# CH32V467VET-USB.net
KiCad netlist of a schematic drawn in Altium Designer
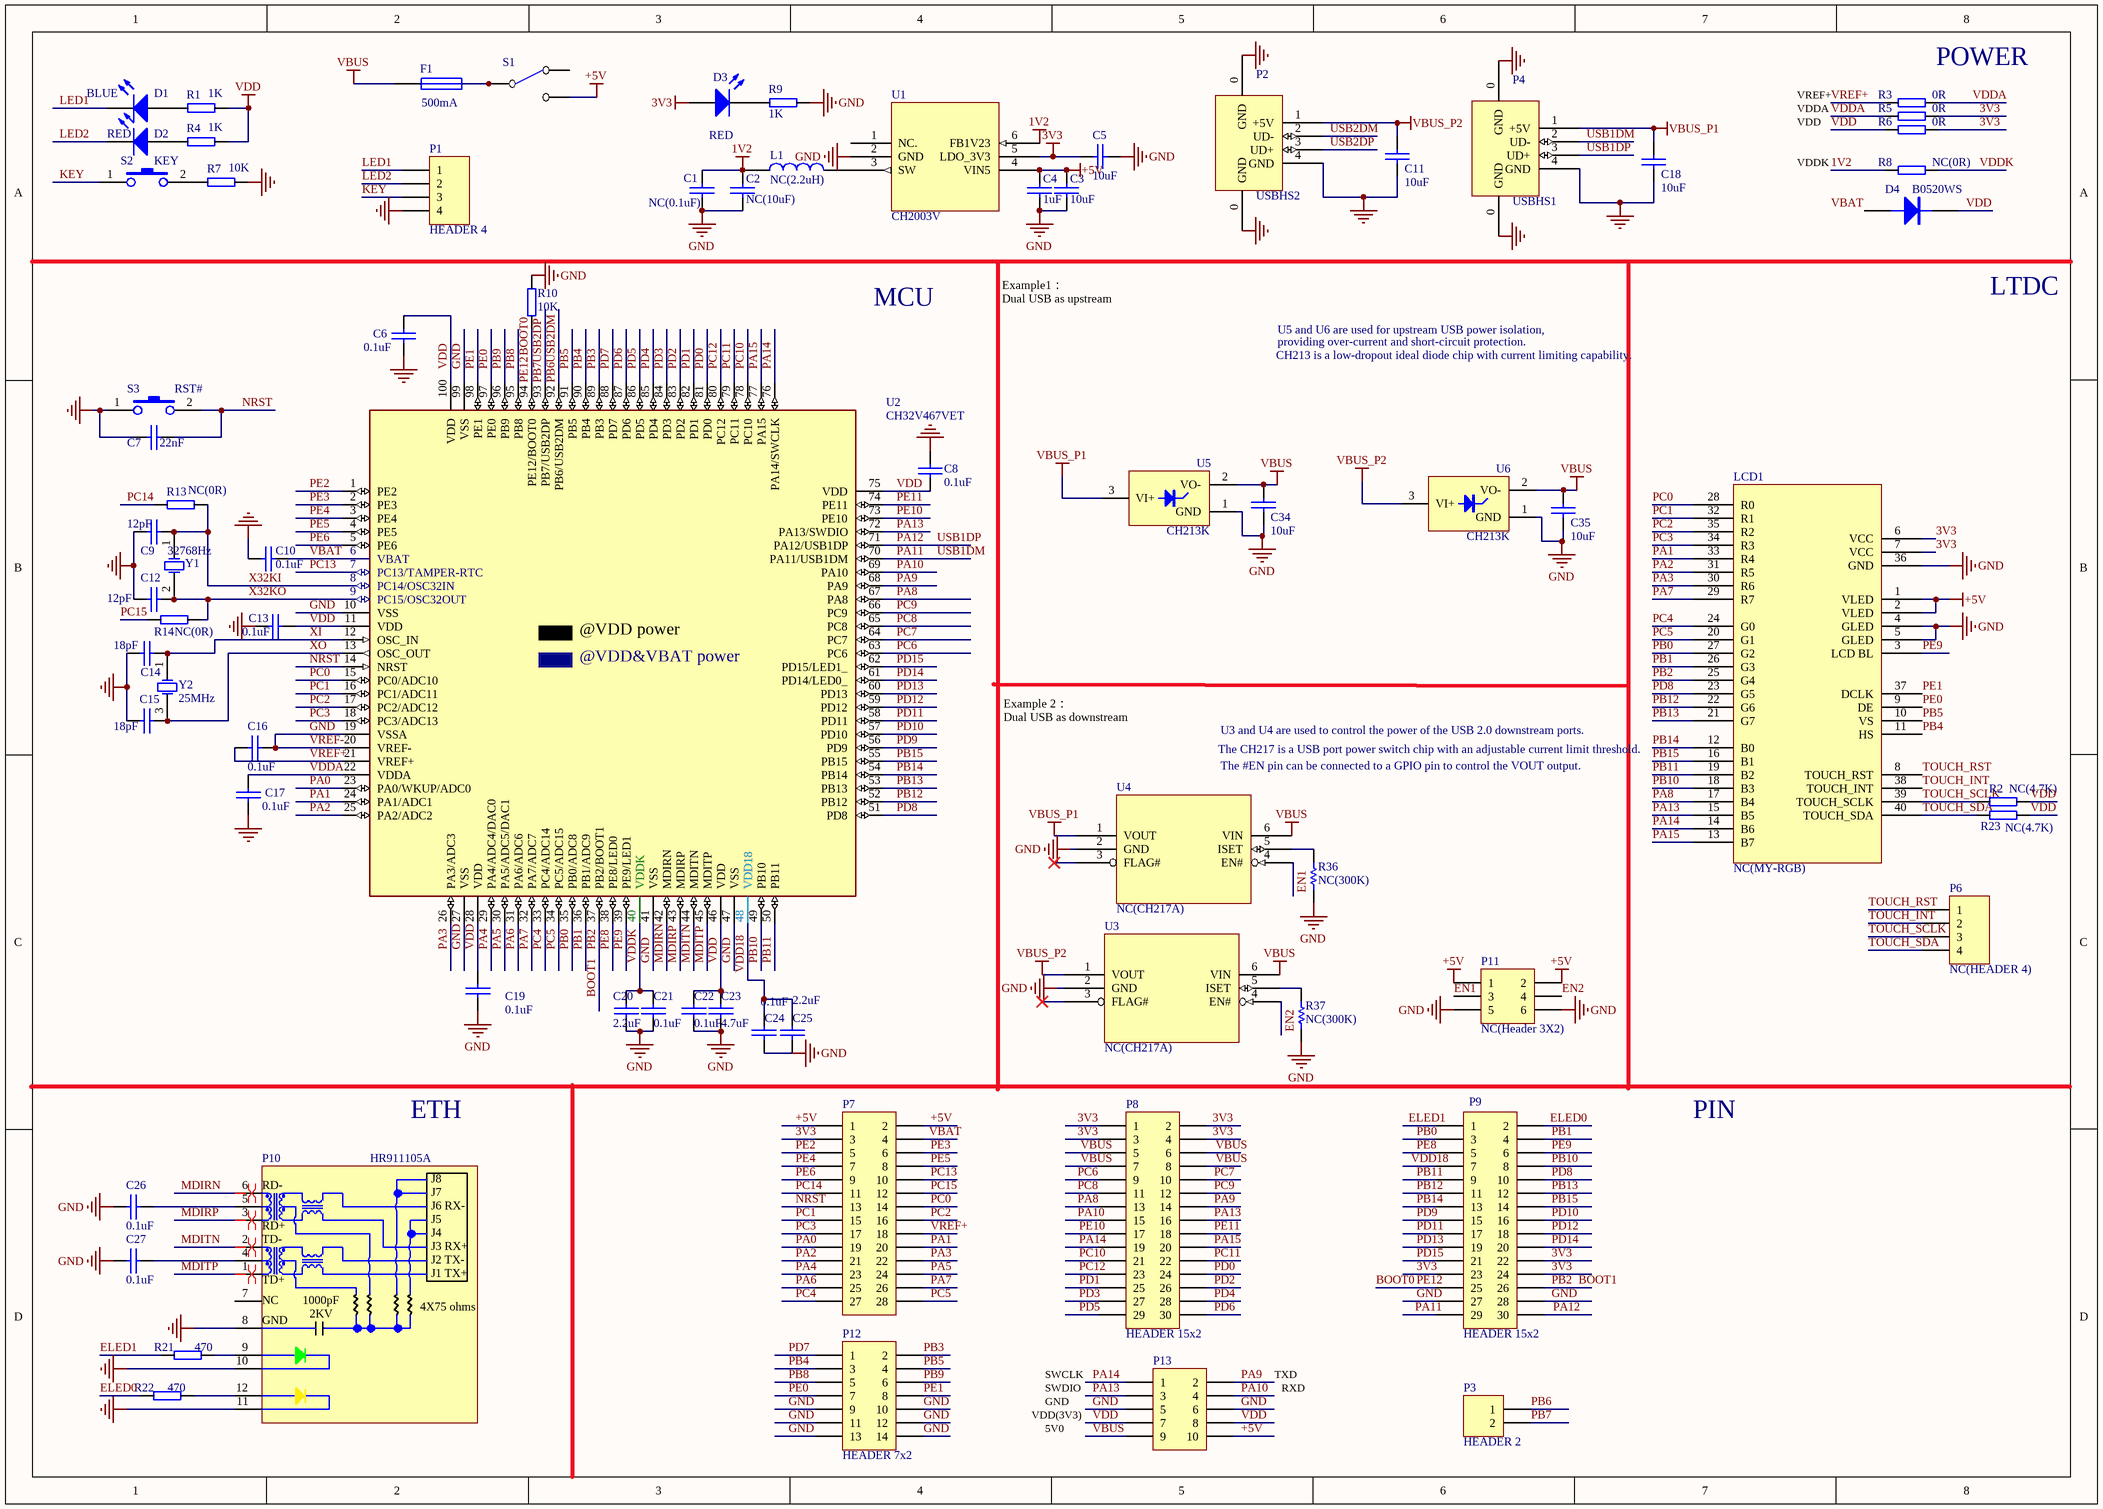
[diagram p0: CH32V467VET-USB.SchDoc]

(export (version "E")
  (design (tool "Eeschema 10.0.6"))
  (components
    (comp (ref "C1")
      (value "NC(0.1uF)")
      (footprint "0402_C")
      (description "Capacitor")
      (libsource (lib "") (part "CAP_2"))
    )
    (comp (ref "C2")
      (value "NC(10uF)")
      (footprint "0603_C")
      (description "Capacitor")
      (libsource (lib "*") (part "CAP"))
    )
    (comp (ref "C3")
      (value "10uF")
      (footprint "0603_C")
      (description "Capacitor")
      (libsource (lib "*") (part "CAP"))
    )
    (comp (ref "C4")
      (value "1uF")
      (footprint "0402_C")
      (description "Capacitor")
      (libsource (lib "") (part "CAP_2"))
    )
    (comp (ref "C5")
      (value "10uF")
      (footprint "0603_C")
      (description "Capacitor")
      (libsource (lib "*") (part "CAP"))
    )
    (comp (ref "C6")
      (value "0.1uF")
      (footprint "0402_C")
      (description "Capacitor")
      (libsource (lib "*") (part "CAP"))
    )
    (comp (ref "C7")
      (value "22nF")
      (footprint "0402_C")
      (description "Capacitor")
      (libsource (lib "") (part "CAP_1"))
    )
    (comp (ref "C8")
      (value "0.1uF")
      (footprint "0402_C")
      (description "Capacitor")
      (libsource (lib "*") (part "CAP"))
    )
    (comp (ref "C9")
      (value "12pF")
      (footprint "0402_C")
      (description "Capacitor")
      (libsource (lib "*") (part "CAP"))
    )
    (comp (ref "C10")
      (value "0.1uF")
      (footprint "0402_C")
      (description "Capacitor")
      (libsource (lib "*") (part "CAP"))
    )
    (comp (ref "C11")
      (value "10uF")
      (footprint "0603_C")
      (description "Capacitor")
      (libsource (lib "") (part "CAP_1"))
    )
    (comp (ref "C12")
      (value "12pF")
      (footprint "0402_C")
      (description "Capacitor")
      (libsource (lib "*") (part "CAP"))
    )
    (comp (ref "C13")
      (value "0.1uF")
      (footprint "0402_C")
      (description "Capacitor")
      (libsource (lib "*") (part "CAP"))
    )
    (comp (ref "C14")
      (value "18pF")
      (footprint "0402_C")
      (description "Capacitor")
      (libsource (lib "*") (part "CAP"))
    )
    (comp (ref "C15")
      (value "18pF")
      (footprint "0402_C")
      (description "Capacitor")
      (libsource (lib "*") (part "CAP"))
    )
    (comp (ref "C16")
      (value "0.1uF")
      (footprint "0402_C")
      (description "Capacitor")
      (libsource (lib "*") (part "CAP"))
    )
    (comp (ref "C17")
      (value "0.1uF")
      (footprint "0402_C")
      (description "Capacitor")
      (libsource (lib "*") (part "CAP"))
    )
    (comp (ref "C18")
      (value "10uF")
      (footprint "0603_C")
      (description "Capacitor")
      (libsource (lib "") (part "CAP_1"))
    )
    (comp (ref "C19")
      (value "0.1uF")
      (footprint "0402_C")
      (description "Capacitor")
      (libsource (lib "*") (part "CAP"))
    )
    (comp (ref "C20")
      (value "2.2uF")
      (footprint "0402_C")
      (description "Capacitor")
      (libsource (lib "*") (part "CAP"))
    )
    (comp (ref "C21")
      (value "0.1uF")
      (footprint "0402_C")
      (description "Capacitor")
      (libsource (lib "*") (part "CAP"))
    )
    (comp (ref "C22")
      (value "0.1uF")
      (footprint "0402_C")
      (description "Capacitor")
      (libsource (lib "*") (part "CAP"))
    )
    (comp (ref "C23")
      (value "4.7uF")
      (footprint "0402_C")
      (description "Capacitor")
      (libsource (lib "*") (part "CAP"))
    )
    (comp (ref "C24")
      (value "0.1uF")
      (footprint "0402_C")
      (description "Capacitor")
      (libsource (lib "*") (part "CAP"))
    )
    (comp (ref "C25")
      (value "2.2uF")
      (footprint "0402_C")
      (description "Capacitor")
      (libsource (lib "*") (part "CAP"))
    )
    (comp (ref "C26")
      (value "0.1uF")
      (footprint "0402_C")
      (description "Capacitor")
      (libsource (lib "wch_sch_others") (part "CAP"))
    )
    (comp (ref "C27")
      (value "0.1uF")
      (footprint "0402_C")
      (description "Capacitor")
      (libsource (lib "wch_sch_others") (part "CAP"))
    )
    (comp (ref "C34")
      (value "10uF")
      (footprint "0603_C")
      (description "Capacitor")
      (libsource (lib "") (part "CAP_1"))
    )
    (comp (ref "C35")
      (value "10uF")
      (footprint "0603_C")
      (description "Capacitor")
      (libsource (lib "") (part "CAP_1"))
    )
    (comp (ref "D1")
      (value "BLUE")
      (footprint "0603+")
      (description "Typical INFRARED GaAs LED")
      (fields (field (name "PUBLISHER") "Altium Limited"))
      (libsource (lib "*") (part "LED0"))
    )
    (comp (ref "D2")
      (value "RED")
      (footprint "0603+")
      (description "Typical INFRARED GaAs LED")
      (fields (field (name "PUBLISHER") "Altium Limited"))
      (libsource (lib "*") (part "LED0"))
    )
    (comp (ref "D3")
      (value "RED")
      (footprint "0603+")
      (description "Typical INFRARED GaAs LED")
      (fields (field (name "PUBLISHER") "Altium Limited"))
      (libsource (lib "*") (part "LED0"))
    )
    (comp (ref "D4")
      (value "B0520WS")
      (footprint "SOD-323")
      (description "Diode")
      (libsource (lib "*") (part "DIODE"))
    )
    (comp (ref "F1")
      (value "500mA")
      (footprint "0603")
      (description "Fuse")
      (libsource (lib "wch_sch_others") (part "FUSE1"))
    )
    (comp (ref "L1") (value "NC(2.2uH)") (footprint "CD32") (libsource (lib "*") (part "INDUCTOR")))
    (comp (ref "LCD1")
      (value "NC(MY-RGB)")
      (footprint "FPC40P-0.5-FK750M3")
      (libsource (lib "MY-显示") (part "MY-RGB"))
    )
    (comp (ref "P1")
      (value "HEADER 4")
      (footprint "SIP4-2.54mm")
      (description "Header, 4-Pin")
      (libsource (lib "wch_sch_others") (part "HEADER 4"))
    )
    (comp (ref "P2")
      (value "USBHS2")
      (footprint "USBAF")
      (description "USB Port")
      (libsource (lib "*") (part "USB"))
    )
    (comp (ref "P3")
      (value "HEADER 2")
      (footprint "MYPCB:SIP2-2.54mm")
      (description "Header, 2-Pin")
      (libsource (lib "wch_sch_others") (part "HEADER 2"))
    )
    (comp (ref "P4")
      (value "USBHS1")
      (footprint "USBAF")
      (description "USB Port")
      (libsource (lib "*") (part "USB"))
    )
    (comp (ref "P6")
      (value "NC(HEADER 4)")
      (footprint "SIP4-2.54mm")
      (description "Header, 4-Pin")
      (libsource (lib "wch_sch_others") (part "HEADER 4"))
    )
    (comp (ref "P7")
      (value "HEADER 14x2")
      (footprint "MYPCB:IDC28-2.54MM")
      (description "Header, 14-Pin, Dual row")
      (libsource (lib "wch_sch_others") (part "HEADER 14x2"))
    )
    (comp (ref "P8")
      (value "HEADER 15x2")
      (footprint "MYPCB:IDC30-2.54MM")
      (description "Header, 15-Pin, Dual row")
      (libsource (lib "wch_sch_others") (part "HEADER 15x2"))
    )
    (comp (ref "P9")
      (value "HEADER 15x2")
      (footprint "MYPCB:IDC30-2.54MM")
      (description "Header, 15-Pin, Dual row")
      (libsource (lib "wch_sch_others") (part "HEADER 15x2"))
    )
    (comp (ref "P10") (value "HR911105A") (footprint "HR911105A") (libsource (lib "*") (part "HR911105A")))
    (comp (ref "P11")
      (value "NC(Header 3X2)")
      (footprint "HDR2X3")
      (description "Header, 3-Pin, Dual row")
      (fields (field (name "PUBLISHER") "Altium Limited"))
      (libsource (lib "Miscellaneous Connectors") (part "Header 3X2"))
    )
    (comp (ref "P12")
      (value "HEADER 7x2")
      (footprint "MYPCB:IDC14-2.54mm")
      (description "Header, 7-Pin, Dual row")
      (libsource (lib "wch_sch_others") (part "HEADER 7x2"))
    )
    (comp (ref "P13")
      (value "LINK")
      (footprint "IDC10-2.54mm")
      (description "Header, 5-Pin, Dual row, Right Angle")
      (fields (field (name "PUBLISHER") "Altium Limited"))
      (libsource (lib "Miscellaneous Connectors") (part "Header 5X2H"))
    )
    (comp (ref "R1") (value "1K") (footprint "0402") (libsource (lib "wch_sch_others") (part "RES")))
    (comp (ref "R2") (value "NC(4.7K)") (footprint "0402") (libsource (lib "wch_sch_others") (part "RES")))
    (comp (ref "R3") (value "0R") (footprint "0402") (libsource (lib "*") (part "R")))
    (comp (ref "R4") (value "1K") (footprint "0402") (libsource (lib "wch_sch_others") (part "RES")))
    (comp (ref "R5") (value "0R") (footprint "0402") (libsource (lib "*") (part "R")))
    (comp (ref "R6") (value "0R") (footprint "0402") (libsource (lib "*") (part "R")))
    (comp (ref "R7") (value "10K") (footprint "0402") (libsource (lib "wch_sch_others") (part "RES")))
    (comp (ref "R8") (value "NC(0R)") (footprint "0402") (libsource (lib "*") (part "R")))
    (comp (ref "R9") (value "1K") (footprint "0402") (libsource (lib "wch_sch_others") (part "RES")))
    (comp (ref "R10") (value "10K") (footprint "0402") (libsource (lib "wch_sch_others") (part "RES")))
    (comp (ref "R13") (value "NC(0R)") (footprint "0402") (libsource (lib "wch_sch_others") (part "RES")))
    (comp (ref "R14") (value "NC(0R)") (footprint "0402") (libsource (lib "wch_sch_others") (part "RES")))
    (comp (ref "R21") (value "470") (footprint "0402") (libsource (lib "wch_sch_others") (part "RES")))
    (comp (ref "R22") (value "470") (footprint "0402") (libsource (lib "wch_sch_others") (part "RES")))
    (comp (ref "R23") (value "NC(4.7K)") (footprint "0402") (libsource (lib "wch_sch_others") (part "RES")))
    (comp (ref "R36")
      (value "NC(300K)")
      (footprint "0603")
      (description "Resistor")
      (fields (field (name "PUBLISHER") "Altium Limited"))
      (libsource (lib "MYLIB") (part "0603-1"))
    )
    (comp (ref "R37")
      (value "NC(300K)")
      (footprint "0603")
      (description "Resistor")
      (fields (field (name "PUBLISHER") "Altium Limited"))
      (libsource (lib "MYLIB") (part "0603-1"))
    )
    (comp (ref "S1") (value "SW SPDT") (footprint "SW1") (libsource (lib "*") (part "SW SPDT")))
    (comp (ref "S2")
      (value "KEY")
      (footprint "SMD_6.1x3.65x2.5mm-KEY")
      (libsource (lib "wch_sch_others") (part "KEY1"))
    )
    (comp (ref "S3")
      (value "RST#")
      (footprint "SMD_6.1x3.65x2.5mm-KEY")
      (libsource (lib "wch_sch_others") (part "KEY1"))
    )
    (comp (ref "U1")
      (value "CH2003V")
      (footprint "SOT-23-6")
      (description "Step-Down DC-DC Converter, 5V input, 1.23V * 800mA output, with LDO 3.3V * 200mA")
      (libsource (lib "CHXXX") (part "CH2003V"))
    )
    (comp (ref "U2")
      (value "CH32V467VET")
      (footprint "LQFP100")
      (description "RISC-V FPU HD-MCU, 175MHz, USB_480M, 100M Ethernet & Phy, CAN, DVP, ADC, DAC, SRAM")
      (libsource (lib "CHXXX") (part "CH32V467VET"))
    )
    (comp (ref "U3")
      (value "NC(CH217A)")
      (footprint "SOT-23-6")
      (description "Current-Limited USB Power Distribution Switch")
      (libsource (lib "CHXXX") (part "CH217K"))
    )
    (comp (ref "U4")
      (value "NC(CH217A)")
      (footprint "SOT-23-6")
      (description "Current-Limited USB Power Distribution Switch")
      (libsource (lib "CHXXX") (part "CH217K"))
    )
    (comp (ref "U5")
      (value "CH213K")
      (footprint "SOT-23-3")
      (description "Ideal Diode 5V*1A")
      (libsource (lib "*") (part "CH213K"))
    )
    (comp (ref "U6")
      (value "CH213K")
      (footprint "SOT-23-3")
      (description "Ideal Diode 5V*1A")
      (libsource (lib "*") (part "CH213K"))
    )
    (comp (ref "Y1")
      (value "32768Hz")
      (footprint "FC-135")
      (description "Crystal Oscillator")
      (fields (field (name "PUBLISHER") "Altium Limited"))
      (libsource (lib "*") (part "XTAL"))
    )
    (comp (ref "Y2")
      (value "25MHz")
      (footprint "XT3225")
      (description "Crystal Oscillator")
      (fields (field (name "PUBLISHER") "Altium Limited"))
      (libsource (lib "") (part "XTAL_1"))
    )
  )
  (nets
    (net (code "1") (name "+5V") (class "Default")
      (node (ref "C3") (pin "2") (pinfunction "2_2") (pintype "passive"))
      (node (ref "C4") (pin "2") (pinfunction "2_2") (pintype "passive"))
      (node (ref "LCD1") (pin "1") (pinfunction "VLED_1") (pintype "passive"))
      (node (ref "LCD1") (pin "2") (pinfunction "VLED_2") (pintype "passive"))
      (node (ref "P11") (pin "1") (pinfunction "1_1") (pintype "passive"))
      (node (ref "P11") (pin "2") (pinfunction "2_2") (pintype "passive"))
      (node (ref "P13") (pin "10") (pinfunction "10_10") (pintype "passive"))
      (node (ref "P7") (pin "1") (pinfunction "1_1") (pintype "passive"))
      (node (ref "P7") (pin "2") (pinfunction "2_2") (pintype "passive"))
      (node (ref "S1") (pin "2") (pinfunction "NC_2") (pintype "passive"))
      (node (ref "U1") (pin "4") (pinfunction "VIN5_4") (pintype "power_in"))
    )
    (net (code "3") (name "/BOOT0") (class "Default")
      (node (ref "P9") (pin "25") (pinfunction "25_25") (pintype "passive"))
      (node (ref "R10") (pin "2") (pintype "passive"))
      (node (ref "U2") (pin "94") (pinfunction "PE12/BOOT0_94") (pintype "bidirectional"))
    )
    (net (code "4") (name "/BOOT1") (class "Default")
      (node (ref "LCD1") (pin "25") (pinfunction "G4_25") (pintype "passive"))
      (node (ref "P9") (pin "26") (pinfunction "26_26") (pintype "passive"))
      (node (ref "U2") (pin "37") (pinfunction "PB2/BOOT1_37") (pintype "bidirectional"))
    )
    (net (code "5") (name "/ELED0") (class "Default")
      (node (ref "P9") (pin "2") (pinfunction "2_2") (pintype "passive"))
      (node (ref "R22") (pin "1") (pintype "passive"))
    )
    (net (code "6") (name "/ELED1") (class "Default")
      (node (ref "P9") (pin "1") (pinfunction "1_1") (pintype "passive"))
      (node (ref "R21") (pin "1") (pintype "passive"))
    )
    (net (code "7") (name "/EN1") (class "Default")
      (node (ref "P11") (pin "3") (pinfunction "3_3") (pintype "passive"))
      (node (ref "U4") (pin "4") (pinfunction "EN#_4") (pintype "input"))
    )
    (net (code "8") (name "/EN2") (class "Default")
      (node (ref "P11") (pin "4") (pinfunction "4_4") (pintype "passive"))
      (node (ref "U3") (pin "4") (pinfunction "EN#_4") (pintype "input"))
    )
    (net (code "9") (name "/KEY") (class "Default")
      (node (ref "P1") (pin "3") (pinfunction "3_3") (pintype "passive"))
      (node (ref "S2") (pin "1") (pinfunction "1_1") (pintype "passive"))
    )
    (net (code "10") (name "/LED1") (class "Default")
      (node (ref "D1") (pin "2") (pinfunction "K_2") (pintype "passive"))
      (node (ref "P1") (pin "1") (pinfunction "1_1") (pintype "passive"))
    )
    (net (code "11") (name "/LED2") (class "Default")
      (node (ref "D2") (pin "2") (pinfunction "K_2") (pintype "passive"))
      (node (ref "P1") (pin "2") (pinfunction "2_2") (pintype "passive"))
    )
    (net (code "12") (name "/MDIRN") (class "Default")
      (node (ref "P10") (pin "6") (pintype "passive"))
      (node (ref "U2") (pin "42") (pinfunction "MDIRN_42") (pintype "bidirectional"))
    )
    (net (code "13") (name "/MDIRP") (class "Default")
      (node (ref "P10") (pin "3") (pintype "passive"))
      (node (ref "U2") (pin "43") (pinfunction "MDIRP_43") (pintype "bidirectional"))
    )
    (net (code "14") (name "/MDITN") (class "Default")
      (node (ref "P10") (pin "2") (pintype "passive"))
      (node (ref "U2") (pin "44") (pinfunction "MDITN_44") (pintype "bidirectional"))
    )
    (net (code "15") (name "/MDITP") (class "Default")
      (node (ref "P10") (pin "1") (pintype "passive"))
      (node (ref "U2") (pin "45") (pinfunction "MDITP_45") (pintype "bidirectional"))
    )
    (net (code "16") (name "/NRST") (class "Default")
      (node (ref "C7") (pin "2") (pinfunction "2_2") (pintype "passive"))
      (node (ref "P7") (pin "13") (pinfunction "13_13") (pintype "passive"))
      (node (ref "S3") (pin "2") (pinfunction "2_2") (pintype "passive"))
      (node (ref "U2") (pin "14") (pinfunction "NRST_14") (pintype "input"))
    )
    (net (code "17") (name "/PA0") (class "Default")
      (node (ref "P7") (pin "19") (pinfunction "19_19") (pintype "passive"))
      (node (ref "U2") (pin "23") (pinfunction "PA0/WKUP/ADC0_23") (pintype "bidirectional"))
    )
    (net (code "18") (name "/PA1") (class "Default")
      (node (ref "LCD1") (pin "33") (pinfunction "R4_33") (pintype "passive"))
      (node (ref "P7") (pin "20") (pinfunction "20_20") (pintype "passive"))
      (node (ref "U2") (pin "24") (pinfunction "PA1/ADC1_24") (pintype "bidirectional"))
    )
    (net (code "19") (name "/PA2") (class "Default")
      (node (ref "LCD1") (pin "31") (pinfunction "R5_31") (pintype "passive"))
      (node (ref "P7") (pin "21") (pinfunction "21_21") (pintype "passive"))
      (node (ref "U2") (pin "25") (pinfunction "PA2/ADC2_25") (pintype "bidirectional"))
    )
    (net (code "20") (name "/PA3") (class "Default")
      (node (ref "LCD1") (pin "30") (pinfunction "R6_30") (pintype "passive"))
      (node (ref "P7") (pin "22") (pinfunction "22_22") (pintype "passive"))
      (node (ref "U2") (pin "26") (pinfunction "PA3/ADC3_26") (pintype "bidirectional"))
    )
    (net (code "21") (name "/PA4") (class "Default")
      (node (ref "P7") (pin "23") (pinfunction "23_23") (pintype "passive"))
      (node (ref "U2") (pin "29") (pinfunction "PA4/ADC4/DAC0_29") (pintype "bidirectional"))
    )
    (net (code "22") (name "/PA5") (class "Default")
      (node (ref "P7") (pin "24") (pinfunction "24_24") (pintype "passive"))
      (node (ref "U2") (pin "30") (pinfunction "PA5/ADC5/DAC1_30") (pintype "bidirectional"))
    )
    (net (code "23") (name "/PA6") (class "Default")
      (node (ref "P7") (pin "25") (pinfunction "25_25") (pintype "passive"))
      (node (ref "U2") (pin "31") (pinfunction "PA6/ADC6_31") (pintype "bidirectional"))
    )
    (net (code "24") (name "/PA7") (class "Default")
      (node (ref "LCD1") (pin "29") (pinfunction "R7_29") (pintype "passive"))
      (node (ref "P7") (pin "26") (pinfunction "26_26") (pintype "passive"))
      (node (ref "U2") (pin "32") (pinfunction "PA7/ADC7_32") (pintype "bidirectional"))
    )
    (net (code "25") (name "/PA8") (class "Default")
      (node (ref "LCD1") (pin "17") (pinfunction "B4_17") (pintype "passive"))
      (node (ref "P8") (pin "13") (pinfunction "13_13") (pintype "passive"))
      (node (ref "U2") (pin "67") (pinfunction "PA8_67") (pintype "bidirectional"))
    )
    (net (code "26") (name "/PA9") (class "Default")
      (node (ref "P13") (pin "2") (pinfunction "2_2") (pintype "passive"))
      (node (ref "P8") (pin "14") (pinfunction "14_14") (pintype "passive"))
      (node (ref "U2") (pin "68") (pinfunction "PA9_68") (pintype "bidirectional"))
    )
    (net (code "27") (name "/PA10") (class "Default")
      (node (ref "P13") (pin "4") (pinfunction "4_4") (pintype "passive"))
      (node (ref "P8") (pin "15") (pinfunction "15_15") (pintype "passive"))
      (node (ref "U2") (pin "69") (pinfunction "PA10_69") (pintype "bidirectional"))
    )
    (net (code "28") (name "/PA11") (class "Default")
      (node (ref "P4") (pin "2") (pinfunction "UD-_2") (pintype "bidirectional"))
      (node (ref "P9") (pin "29") (pinfunction "29_29") (pintype "passive"))
      (node (ref "U2") (pin "70") (pinfunction "PA11/USB1DM_70") (pintype "bidirectional"))
    )
    (net (code "29") (name "/PA12") (class "Default")
      (node (ref "P4") (pin "3") (pinfunction "UD+_3") (pintype "bidirectional"))
      (node (ref "P9") (pin "30") (pinfunction "30_30") (pintype "passive"))
      (node (ref "U2") (pin "71") (pinfunction "PA12/USB1DP_71") (pintype "bidirectional"))
    )
    (net (code "30") (name "/PA13") (class "Default")
      (node (ref "LCD1") (pin "15") (pinfunction "B5_15") (pintype "passive"))
      (node (ref "P13") (pin "3") (pinfunction "3_3") (pintype "passive"))
      (node (ref "P8") (pin "16") (pinfunction "16_16") (pintype "passive"))
      (node (ref "U2") (pin "72") (pinfunction "PA13/SWDIO_72") (pintype "bidirectional"))
    )
    (net (code "31") (name "/PA14") (class "Default")
      (node (ref "LCD1") (pin "14") (pinfunction "B6_14") (pintype "passive"))
      (node (ref "P13") (pin "1") (pinfunction "1_1") (pintype "passive"))
      (node (ref "P8") (pin "19") (pinfunction "19_19") (pintype "passive"))
      (node (ref "U2") (pin "76") (pinfunction "PA14/SWCLK_76") (pintype "bidirectional"))
    )
    (net (code "32") (name "/PA15") (class "Default")
      (node (ref "LCD1") (pin "13") (pinfunction "B7_13") (pintype "passive"))
      (node (ref "P8") (pin "20") (pinfunction "20_20") (pintype "passive"))
      (node (ref "U2") (pin "77") (pinfunction "PA15_77") (pintype "bidirectional"))
    )
    (net (code "33") (name "/PB0") (class "Default")
      (node (ref "LCD1") (pin "27") (pinfunction "G2_27") (pintype "passive"))
      (node (ref "P9") (pin "3") (pinfunction "3_3") (pintype "passive"))
      (node (ref "U2") (pin "35") (pinfunction "PB0/ADC8_35") (pintype "bidirectional"))
    )
    (net (code "34") (name "/PB1") (class "Default")
      (node (ref "LCD1") (pin "26") (pinfunction "G3_26") (pintype "passive"))
      (node (ref "P9") (pin "4") (pinfunction "4_4") (pintype "passive"))
      (node (ref "U2") (pin "36") (pinfunction "PB1/ADC9_36") (pintype "bidirectional"))
    )
    (net (code "35") (name "/PB3") (class "Default")
      (node (ref "P12") (pin "2") (pinfunction "2_2") (pintype "passive"))
      (node (ref "U2") (pin "89") (pinfunction "PB3_89") (pintype "bidirectional"))
    )
    (net (code "36") (name "/PB4") (class "Default")
      (node (ref "LCD1") (pin "11") (pinfunction "HS_11") (pintype "passive"))
      (node (ref "P12") (pin "3") (pinfunction "3_3") (pintype "passive"))
      (node (ref "U2") (pin "90") (pinfunction "PB4_90") (pintype "bidirectional"))
    )
    (net (code "37") (name "/PB5") (class "Default")
      (node (ref "LCD1") (pin "10") (pinfunction "VS_10") (pintype "passive"))
      (node (ref "P12") (pin "4") (pinfunction "4_4") (pintype "passive"))
      (node (ref "U2") (pin "91") (pinfunction "PB5_91") (pintype "bidirectional"))
    )
    (net (code "38") (name "/PB6") (class "Default")
      (node (ref "P2") (pin "2") (pinfunction "UD-_2") (pintype "bidirectional"))
      (node (ref "P3") (pin "1") (pinfunction "1_1") (pintype "passive"))
      (node (ref "U2") (pin "92") (pinfunction "PB6/USB2DM_92") (pintype "bidirectional"))
    )
    (net (code "39") (name "/PB7") (class "Default")
      (node (ref "P2") (pin "3") (pinfunction "UD+_3") (pintype "bidirectional"))
      (node (ref "P3") (pin "2") (pinfunction "2_2") (pintype "passive"))
      (node (ref "U2") (pin "93") (pinfunction "PB7/USB2DP_93") (pintype "bidirectional"))
    )
    (net (code "40") (name "/PB8") (class "Default")
      (node (ref "P12") (pin "5") (pinfunction "5_5") (pintype "passive"))
      (node (ref "U2") (pin "95") (pinfunction "PB8_95") (pintype "bidirectional"))
    )
    (net (code "41") (name "/PB9") (class "Default")
      (node (ref "P12") (pin "6") (pinfunction "6_6") (pintype "passive"))
      (node (ref "U2") (pin "96") (pinfunction "PB9_96") (pintype "bidirectional"))
    )
    (net (code "42") (name "/PB10") (class "Default")
      (node (ref "LCD1") (pin "18") (pinfunction "B3_18") (pintype "passive"))
      (node (ref "P9") (pin "8") (pinfunction "8_8") (pintype "passive"))
      (node (ref "U2") (pin "49") (pinfunction "PB10_49") (pintype "bidirectional"))
    )
    (net (code "43") (name "/PB11") (class "Default")
      (node (ref "LCD1") (pin "19") (pinfunction "B2_19") (pintype "passive"))
      (node (ref "P9") (pin "9") (pinfunction "9_9") (pintype "passive"))
      (node (ref "U2") (pin "50") (pinfunction "PB11_50") (pintype "bidirectional"))
    )
    (net (code "44") (name "/PB12") (class "Default")
      (node (ref "LCD1") (pin "22") (pinfunction "G6_22") (pintype "passive"))
      (node (ref "P9") (pin "11") (pinfunction "11_11") (pintype "passive"))
      (node (ref "U2") (pin "52") (pinfunction "PB12_52") (pintype "bidirectional"))
    )
    (net (code "45") (name "/PB13") (class "Default")
      (node (ref "LCD1") (pin "21") (pinfunction "G7_21") (pintype "passive"))
      (node (ref "P9") (pin "12") (pinfunction "12_12") (pintype "passive"))
      (node (ref "U2") (pin "53") (pinfunction "PB13_53") (pintype "bidirectional"))
    )
    (net (code "46") (name "/PB14") (class "Default")
      (node (ref "LCD1") (pin "12") (pinfunction "B0_12") (pintype "passive"))
      (node (ref "P9") (pin "13") (pinfunction "13_13") (pintype "passive"))
      (node (ref "U2") (pin "54") (pinfunction "PB14_54") (pintype "bidirectional"))
    )
    (net (code "47") (name "/PB15") (class "Default")
      (node (ref "LCD1") (pin "16") (pinfunction "B1_16") (pintype "passive"))
      (node (ref "P9") (pin "14") (pinfunction "14_14") (pintype "passive"))
      (node (ref "U2") (pin "55") (pinfunction "PB15_55") (pintype "bidirectional"))
    )
    (net (code "48") (name "/PC0") (class "Default")
      (node (ref "LCD1") (pin "28") (pinfunction "R0_28") (pintype "passive"))
      (node (ref "P7") (pin "14") (pinfunction "14_14") (pintype "passive"))
      (node (ref "U2") (pin "15") (pinfunction "PC0/ADC10_15") (pintype "bidirectional"))
    )
    (net (code "49") (name "/PC1") (class "Default")
      (node (ref "LCD1") (pin "32") (pinfunction "R1_32") (pintype "passive"))
      (node (ref "P7") (pin "15") (pinfunction "15_15") (pintype "passive"))
      (node (ref "U2") (pin "16") (pinfunction "PC1/ADC11_16") (pintype "bidirectional"))
    )
    (net (code "50") (name "/PC2") (class "Default")
      (node (ref "LCD1") (pin "35") (pinfunction "R2_35") (pintype "passive"))
      (node (ref "P7") (pin "16") (pinfunction "16_16") (pintype "passive"))
      (node (ref "U2") (pin "17") (pinfunction "PC2/ADC12_17") (pintype "bidirectional"))
    )
    (net (code "51") (name "/PC3") (class "Default")
      (node (ref "LCD1") (pin "34") (pinfunction "R3_34") (pintype "passive"))
      (node (ref "P7") (pin "17") (pinfunction "17_17") (pintype "passive"))
      (node (ref "U2") (pin "18") (pinfunction "PC3/ADC13_18") (pintype "bidirectional"))
    )
    (net (code "52") (name "/PC4") (class "Default")
      (node (ref "LCD1") (pin "24") (pinfunction "G0_24") (pintype "passive"))
      (node (ref "P7") (pin "27") (pinfunction "27_27") (pintype "passive"))
      (node (ref "U2") (pin "33") (pinfunction "PC4/ADC14_33") (pintype "bidirectional"))
    )
    (net (code "53") (name "/PC5") (class "Default")
      (node (ref "LCD1") (pin "20") (pinfunction "G1_20") (pintype "passive"))
      (node (ref "P7") (pin "28") (pinfunction "28_28") (pintype "passive"))
      (node (ref "U2") (pin "34") (pinfunction "PC5/ADC15_34") (pintype "bidirectional"))
    )
    (net (code "54") (name "/PC6") (class "Default")
      (node (ref "P8") (pin "9") (pinfunction "9_9") (pintype "passive"))
      (node (ref "U2") (pin "63") (pinfunction "PC6_63") (pintype "bidirectional"))
    )
    (net (code "55") (name "/PC7") (class "Default")
      (node (ref "P8") (pin "10") (pinfunction "10_10") (pintype "passive"))
      (node (ref "U2") (pin "64") (pinfunction "PC7_64") (pintype "bidirectional"))
    )
    (net (code "56") (name "/PC8") (class "Default")
      (node (ref "P8") (pin "11") (pinfunction "11_11") (pintype "passive"))
      (node (ref "U2") (pin "65") (pinfunction "PC8_65") (pintype "bidirectional"))
    )
    (net (code "57") (name "/PC9") (class "Default")
      (node (ref "P8") (pin "12") (pinfunction "12_12") (pintype "passive"))
      (node (ref "U2") (pin "66") (pinfunction "PC9_66") (pintype "bidirectional"))
    )
    (net (code "58") (name "/PC10") (class "Default")
      (node (ref "P8") (pin "21") (pinfunction "21_21") (pintype "passive"))
      (node (ref "U2") (pin "78") (pinfunction "PC10_78") (pintype "bidirectional"))
    )
    (net (code "59") (name "/PC11") (class "Default")
      (node (ref "P8") (pin "22") (pinfunction "22_22") (pintype "passive"))
      (node (ref "U2") (pin "79") (pinfunction "PC11_79") (pintype "bidirectional"))
    )
    (net (code "60") (name "/PC12") (class "Default")
      (node (ref "P8") (pin "23") (pinfunction "23_23") (pintype "passive"))
      (node (ref "U2") (pin "80") (pinfunction "PC12_80") (pintype "bidirectional"))
    )
    (net (code "61") (name "/PC13") (class "Default")
      (node (ref "P7") (pin "10") (pinfunction "10_10") (pintype "passive"))
      (node (ref "U2") (pin "7") (pinfunction "PC13/TAMPER-RTC_7") (pintype "bidirectional"))
    )
    (net (code "62") (name "/PC14") (class "Default")
      (node (ref "P7") (pin "11") (pinfunction "11_11") (pintype "passive"))
      (node (ref "R13") (pin "1") (pintype "passive"))
    )
    (net (code "63") (name "/PC15") (class "Default")
      (node (ref "P7") (pin "12") (pinfunction "12_12") (pintype "passive"))
      (node (ref "R14") (pin "1") (pintype "passive"))
    )
    (net (code "64") (name "/PD0") (class "Default")
      (node (ref "P8") (pin "24") (pinfunction "24_24") (pintype "passive"))
      (node (ref "U2") (pin "81") (pinfunction "PD0_81") (pintype "bidirectional"))
    )
    (net (code "65") (name "/PD1") (class "Default")
      (node (ref "P8") (pin "25") (pinfunction "25_25") (pintype "passive"))
      (node (ref "U2") (pin "82") (pinfunction "PD1_82") (pintype "bidirectional"))
    )
    (net (code "66") (name "/PD2") (class "Default")
      (node (ref "P8") (pin "26") (pinfunction "26_26") (pintype "passive"))
      (node (ref "U2") (pin "83") (pinfunction "PD2_83") (pintype "bidirectional"))
    )
    (net (code "67") (name "/PD3") (class "Default")
      (node (ref "P8") (pin "27") (pinfunction "27_27") (pintype "passive"))
      (node (ref "U2") (pin "84") (pinfunction "PD3_84") (pintype "bidirectional"))
    )
    (net (code "68") (name "/PD4") (class "Default")
      (node (ref "P8") (pin "28") (pinfunction "28_28") (pintype "passive"))
      (node (ref "U2") (pin "85") (pinfunction "PD4_85") (pintype "bidirectional"))
    )
    (net (code "69") (name "/PD5") (class "Default")
      (node (ref "P8") (pin "29") (pinfunction "29_29") (pintype "passive"))
      (node (ref "U2") (pin "86") (pinfunction "PD5_86") (pintype "bidirectional"))
    )
    (net (code "70") (name "/PD6") (class "Default")
      (node (ref "P8") (pin "30") (pinfunction "30_30") (pintype "passive"))
      (node (ref "U2") (pin "87") (pinfunction "PD6_87") (pintype "bidirectional"))
    )
    (net (code "71") (name "/PD7") (class "Default")
      (node (ref "P12") (pin "1") (pinfunction "1_1") (pintype "passive"))
      (node (ref "U2") (pin "88") (pinfunction "PD7_88") (pintype "bidirectional"))
    )
    (net (code "72") (name "/PD8") (class "Default")
      (node (ref "LCD1") (pin "23") (pinfunction "G5_23") (pintype "passive"))
      (node (ref "P9") (pin "10") (pinfunction "10_10") (pintype "passive"))
      (node (ref "U2") (pin "51") (pinfunction "PD8_51") (pintype "bidirectional"))
    )
    (net (code "73") (name "/PD9") (class "Default")
      (node (ref "P9") (pin "15") (pinfunction "15_15") (pintype "passive"))
      (node (ref "U2") (pin "56") (pinfunction "PD9_56") (pintype "bidirectional"))
    )
    (net (code "74") (name "/PD10") (class "Default")
      (node (ref "P9") (pin "16") (pinfunction "16_16") (pintype "passive"))
      (node (ref "U2") (pin "57") (pinfunction "PD10_57") (pintype "bidirectional"))
    )
    (net (code "75") (name "/PD11") (class "Default")
      (node (ref "P9") (pin "17") (pinfunction "17_17") (pintype "passive"))
      (node (ref "U2") (pin "58") (pinfunction "PD11_58") (pintype "bidirectional"))
    )
    (net (code "76") (name "/PD12") (class "Default")
      (node (ref "P9") (pin "18") (pinfunction "18_18") (pintype "passive"))
      (node (ref "U2") (pin "59") (pinfunction "PD12_59") (pintype "bidirectional"))
    )
    (net (code "77") (name "/PD13") (class "Default")
      (node (ref "P9") (pin "19") (pinfunction "19_19") (pintype "passive"))
      (node (ref "U2") (pin "60") (pinfunction "PD13_60") (pintype "bidirectional"))
    )
    (net (code "78") (name "/PD14") (class "Default")
      (node (ref "P9") (pin "20") (pinfunction "20_20") (pintype "passive"))
      (node (ref "U2") (pin "61") (pinfunction "PD14/LED0__61") (pintype "bidirectional"))
    )
    (net (code "79") (name "/PD15") (class "Default")
      (node (ref "P9") (pin "21") (pinfunction "21_21") (pintype "passive"))
      (node (ref "U2") (pin "62") (pinfunction "PD15/LED1__62") (pintype "bidirectional"))
    )
    (net (code "80") (name "/PE0") (class "Default")
      (node (ref "LCD1") (pin "9") (pinfunction "DE_9") (pintype "passive"))
      (node (ref "P12") (pin "7") (pinfunction "7_7") (pintype "passive"))
      (node (ref "U2") (pin "97") (pinfunction "PE0_97") (pintype "bidirectional"))
    )
    (net (code "81") (name "/PE1") (class "Default")
      (node (ref "LCD1") (pin "37") (pinfunction "DCLK_37") (pintype "passive"))
      (node (ref "P12") (pin "8") (pinfunction "8_8") (pintype "passive"))
      (node (ref "U2") (pin "98") (pinfunction "PE1_98") (pintype "bidirectional"))
    )
    (net (code "82") (name "/PE2") (class "Default")
      (node (ref "P7") (pin "5") (pinfunction "5_5") (pintype "passive"))
      (node (ref "U2") (pin "1") (pinfunction "PE2_1") (pintype "bidirectional"))
    )
    (net (code "83") (name "/PE3") (class "Default")
      (node (ref "P7") (pin "6") (pinfunction "6_6") (pintype "passive"))
      (node (ref "U2") (pin "2") (pinfunction "PE3_2") (pintype "bidirectional"))
    )
    (net (code "84") (name "/PE4") (class "Default")
      (node (ref "P7") (pin "7") (pinfunction "7_7") (pintype "passive"))
      (node (ref "U2") (pin "3") (pinfunction "PE4_3") (pintype "bidirectional"))
    )
    (net (code "85") (name "/PE5") (class "Default")
      (node (ref "P7") (pin "8") (pinfunction "8_8") (pintype "passive"))
      (node (ref "U2") (pin "4") (pinfunction "PE5_4") (pintype "bidirectional"))
    )
    (net (code "86") (name "/PE6") (class "Default")
      (node (ref "P7") (pin "9") (pinfunction "9_9") (pintype "passive"))
      (node (ref "U2") (pin "5") (pinfunction "PE6_5") (pintype "bidirectional"))
    )
    (net (code "87") (name "/PE8") (class "Default")
      (node (ref "P9") (pin "5") (pinfunction "5_5") (pintype "passive"))
      (node (ref "U2") (pin "38") (pinfunction "PE8/LED0_38") (pintype "bidirectional"))
    )
    (net (code "88") (name "/PE9") (class "Default")
      (node (ref "LCD1") (pin "3") (pinfunction "LCD_BL_3") (pintype "passive"))
      (node (ref "P9") (pin "6") (pinfunction "6_6") (pintype "passive"))
      (node (ref "U2") (pin "39") (pinfunction "PE9/LED1_39") (pintype "bidirectional"))
    )
    (net (code "89") (name "/PE10") (class "Default")
      (node (ref "P8") (pin "17") (pinfunction "17_17") (pintype "passive"))
      (node (ref "U2") (pin "73") (pinfunction "PE10_73") (pintype "bidirectional"))
    )
    (net (code "90") (name "/PE11") (class "Default")
      (node (ref "P8") (pin "18") (pinfunction "18_18") (pintype "passive"))
      (node (ref "U2") (pin "74") (pinfunction "PE11_74") (pintype "bidirectional"))
    )
    (net (code "91") (name "/TOUCH_INT") (class "Default")
      (node (ref "LCD1") (pin "38") (pinfunction "TOUCH_INT_38") (pintype "passive"))
      (node (ref "P6") (pin "2") (pinfunction "2_2") (pintype "passive"))
    )
    (net (code "92") (name "/TOUCH_RST") (class "Default")
      (node (ref "LCD1") (pin "8") (pinfunction "TOUCH_RST_8") (pintype "passive"))
      (node (ref "P6") (pin "1") (pinfunction "1_1") (pintype "passive"))
    )
    (net (code "93") (name "/TOUCH_SCLK") (class "Default")
      (node (ref "LCD1") (pin "39") (pinfunction "TOUCH_SCLK_39") (pintype "passive"))
      (node (ref "P6") (pin "3") (pinfunction "3_3") (pintype "passive"))
      (node (ref "R2") (pin "2") (pintype "passive"))
    )
    (net (code "94") (name "/TOUCH_SDA") (class "Default")
      (node (ref "LCD1") (pin "40") (pinfunction "TOUCH_SDA_40") (pintype "passive"))
      (node (ref "P6") (pin "4") (pinfunction "4_4") (pintype "passive"))
      (node (ref "R23") (pin "2") (pintype "passive"))
    )
    (net (code "95") (name "/VBAT") (class "Default")
      (node (ref "C10") (pin "2") (pinfunction "2_2") (pintype "passive"))
      (node (ref "P7") (pin "4") (pinfunction "4_4") (pintype "passive"))
      (node (ref "U2") (pin "6") (pinfunction "VBAT_6") (pintype "power_in"))
    )
    (net (code "96") (name "/VDD18") (class "Default")
      (node (ref "C24") (pin "2") (pinfunction "2_2") (pintype "passive"))
      (node (ref "C25") (pin "2") (pinfunction "2_2") (pintype "passive"))
      (node (ref "P9") (pin "7") (pinfunction "7_7") (pintype "passive"))
      (node (ref "U2") (pin "48") (pinfunction "VDD18_48") (pintype "power_in"))
    )
    (net (code "97") (name "/VDDA") (class "Default")
      (node (ref "C17") (pin "1") (pinfunction "1_1") (pintype "passive"))
      (node (ref "R3") (pin "1") (pinfunction "1_1") (pintype "passive"))
      (node (ref "R5") (pin "2") (pinfunction "2_2") (pintype "passive"))
      (node (ref "U2") (pin "22") (pinfunction "VDDA_22") (pintype "power_in"))
    )
    (net (code "98") (name "/VDDK") (class "Default")
      (node (ref "C20") (pin "2") (pinfunction "2_2") (pintype "passive"))
      (node (ref "C21") (pin "2") (pinfunction "2_2") (pintype "passive"))
      (node (ref "R8") (pin "1") (pinfunction "1_1") (pintype "passive"))
      (node (ref "U2") (pin "40") (pinfunction "VDDK_40") (pintype "power_in"))
    )
    (net (code "99") (name "/VREF+") (class "Default")
      (node (ref "C16") (pin "1") (pinfunction "1_1") (pintype "passive"))
      (node (ref "P7") (pin "18") (pinfunction "18_18") (pintype "passive"))
      (node (ref "R3") (pin "2") (pinfunction "2_2") (pintype "passive"))
      (node (ref "U2") (pin "21") (pinfunction "VREF+_21") (pintype "power_in"))
    )
    (net (code "100") (name "/X32KI") (class "Default")
      (node (ref "C9") (pin "2") (pinfunction "2_2") (pintype "passive"))
      (node (ref "R13") (pin "2") (pintype "passive"))
      (node (ref "U2") (pin "8") (pinfunction "PC14/OSC32IN_8") (pintype "bidirectional"))
      (node (ref "Y1") (pin "1") (pinfunction "OSC1_1") (pintype "passive"))
    )
    (net (code "101") (name "/X32KO") (class "Default")
      (node (ref "C12") (pin "2") (pinfunction "2_2") (pintype "passive"))
      (node (ref "R14") (pin "2") (pintype "passive"))
      (node (ref "U2") (pin "9") (pinfunction "PC15/OSC32OUT_9") (pintype "bidirectional"))
      (node (ref "Y1") (pin "2") (pinfunction "OSC2_2") (pintype "passive"))
    )
    (net (code "102") (name "/XI") (class "Default")
      (node (ref "C14") (pin "2") (pinfunction "2_2") (pintype "passive"))
      (node (ref "U2") (pin "12") (pinfunction "OSC_IN_12") (pintype "input"))
      (node (ref "Y2") (pin "1") (pinfunction "OSC1_1") (pintype "passive"))
    )
    (net (code "103") (name "/XO") (class "Default")
      (node (ref "C15") (pin "2") (pinfunction "2_2") (pintype "passive"))
      (node (ref "U2") (pin "13") (pinfunction "OSC_OUT_13") (pintype "output"))
      (node (ref "Y2") (pin "3") (pinfunction "OSC2_3") (pintype "passive"))
    )
    (net (code "104") (name "1V2") (class "Default")
      (node (ref "C1") (pin "2") (pinfunction "2_2") (pintype "passive"))
      (node (ref "C2") (pin "2") (pinfunction "2_2") (pintype "passive"))
      (node (ref "L1") (pin "2") (pinfunction "2_2") (pintype "passive"))
      (node (ref "R8") (pin "2") (pinfunction "2_2") (pintype "passive"))
      (node (ref "U1") (pin "6") (pinfunction "FB1V23_6") (pintype "input"))
    )
    (net (code "105") (name "3V3") (class "Default")
      (node (ref "C5") (pin "2") (pinfunction "2_2") (pintype "passive"))
      (node (ref "D3") (pin "1") (pinfunction "A_1") (pintype "passive"))
      (node (ref "LCD1") (pin "6") (pinfunction "VCC_6") (pintype "passive"))
      (node (ref "LCD1") (pin "7") (pinfunction "VCC_7") (pintype "passive"))
      (node (ref "P7") (pin "3") (pinfunction "3_3") (pintype "passive"))
      (node (ref "P8") (pin "1") (pinfunction "1_1") (pintype "passive"))
      (node (ref "P8") (pin "2") (pinfunction "2_2") (pintype "passive"))
      (node (ref "P8") (pin "3") (pinfunction "3_3") (pintype "passive"))
      (node (ref "P8") (pin "4") (pinfunction "4_4") (pintype "passive"))
      (node (ref "P9") (pin "22") (pinfunction "22_22") (pintype "passive"))
      (node (ref "P9") (pin "23") (pinfunction "23_23") (pintype "passive"))
      (node (ref "P9") (pin "24") (pinfunction "24_24") (pintype "passive"))
      (node (ref "R5") (pin "1") (pinfunction "1_1") (pintype "passive"))
      (node (ref "R6") (pin "1") (pinfunction "1_1") (pintype "passive"))
      (node (ref "U1") (pin "5") (pinfunction "LDO_3V3_5") (pintype "power_in"))
    )
    (net (code "106") (name "GND") (class "Default")
      (node (ref "C1") (pin "1") (pinfunction "1_1") (pintype "passive"))
      (node (ref "C10") (pin "1") (pinfunction "1_1") (pintype "passive"))
      (node (ref "C11") (pin "2") (pinfunction "2_2") (pintype "passive"))
      (node (ref "C12") (pin "1") (pinfunction "1_1") (pintype "passive"))
      (node (ref "C13") (pin "2") (pinfunction "2_2") (pintype "passive"))
      (node (ref "C14") (pin "1") (pinfunction "1_1") (pintype "passive"))
      (node (ref "C15") (pin "1") (pinfunction "1_1") (pintype "passive"))
      (node (ref "C16") (pin "2") (pinfunction "2_2") (pintype "passive"))
      (node (ref "C17") (pin "2") (pinfunction "2_2") (pintype "passive"))
      (node (ref "C18") (pin "2") (pinfunction "2_2") (pintype "passive"))
      (node (ref "C19") (pin "1") (pinfunction "1_1") (pintype "passive"))
      (node (ref "C2") (pin "1") (pinfunction "1_1") (pintype "passive"))
      (node (ref "C20") (pin "1") (pinfunction "1_1") (pintype "passive"))
      (node (ref "C21") (pin "1") (pinfunction "1_1") (pintype "passive"))
      (node (ref "C22") (pin "1") (pinfunction "1_1") (pintype "passive"))
      (node (ref "C23") (pin "1") (pinfunction "1_1") (pintype "passive"))
      (node (ref "C25") (pin "1") (pinfunction "1_1") (pintype "passive"))
      (node (ref "C26") (pin "1") (pinfunction "1_1") (pintype "passive"))
      (node (ref "C27") (pin "1") (pinfunction "1_1") (pintype "passive"))
      (node (ref "C3") (pin "1") (pinfunction "1_1") (pintype "passive"))
      (node (ref "C34") (pin "2") (pinfunction "2_2") (pintype "passive"))
      (node (ref "C35") (pin "2") (pinfunction "2_2") (pintype "passive"))
      (node (ref "C4") (pin "1") (pinfunction "1_1") (pintype "passive"))
      (node (ref "C5") (pin "1") (pinfunction "1_1") (pintype "passive"))
      (node (ref "C6") (pin "1") (pinfunction "1_1") (pintype "passive"))
      (node (ref "C7") (pin "1") (pinfunction "1_1") (pintype "passive"))
      (node (ref "C8") (pin "2") (pinfunction "2_2") (pintype "passive"))
      (node (ref "C9") (pin "1") (pinfunction "1_1") (pintype "passive"))
      (node (ref "LCD1") (pin "36") (pinfunction "GND_36") (pintype "passive"))
      (node (ref "LCD1") (pin "4") (pinfunction "GLED_4") (pintype "passive"))
      (node (ref "LCD1") (pin "5") (pinfunction "GLED_5") (pintype "passive"))
      (node (ref "P1") (pin "4") (pinfunction "4_4") (pintype "passive"))
      (node (ref "P10") (pin "10") (pintype "passive"))
      (node (ref "P10") (pin "11") (pintype "passive"))
      (node (ref "P10") (pin "8") (pintype "passive"))
      (node (ref "P11") (pin "5") (pinfunction "5_5") (pintype "passive"))
      (node (ref "P11") (pin "6") (pinfunction "6_6") (pintype "passive"))
      (node (ref "P12") (pin "10") (pinfunction "10_10") (pintype "passive"))
      (node (ref "P12") (pin "11") (pinfunction "11_11") (pintype "passive"))
      (node (ref "P12") (pin "12") (pinfunction "12_12") (pintype "passive"))
      (node (ref "P12") (pin "13") (pinfunction "13_13") (pintype "passive"))
      (node (ref "P12") (pin "14") (pinfunction "14_14") (pintype "passive"))
      (node (ref "P12") (pin "9") (pinfunction "9_9") (pintype "passive"))
      (node (ref "P13") (pin "5") (pinfunction "5_5") (pintype "passive"))
      (node (ref "P13") (pin "6") (pinfunction "6_6") (pintype "passive"))
      (node (ref "P2") (pin "0") (pinfunction "GND_0") (pintype "power_in"))
      (node (ref "P2") (pin "4") (pinfunction "GND_4") (pintype "power_in"))
      (node (ref "P4") (pin "0") (pinfunction "GND_0") (pintype "power_in"))
      (node (ref "P4") (pin "4") (pinfunction "GND_4") (pintype "power_in"))
      (node (ref "P9") (pin "27") (pinfunction "27_27") (pintype "passive"))
      (node (ref "P9") (pin "28") (pinfunction "28_28") (pintype "passive"))
      (node (ref "R10") (pin "1") (pintype "passive"))
      (node (ref "R36") (pin "2") (pinfunction "2_2") (pintype "passive"))
      (node (ref "R37") (pin "2") (pinfunction "2_2") (pintype "passive"))
      (node (ref "R7") (pin "1") (pintype "passive"))
      (node (ref "R9") (pin "2") (pintype "passive"))
      (node (ref "S3") (pin "1") (pinfunction "1_1") (pintype "passive"))
      (node (ref "U1") (pin "2") (pinfunction "GND_2") (pintype "power_in"))
      (node (ref "U2") (pin "10") (pinfunction "VSS_10") (pintype "power_in"))
      (node (ref "U2") (pin "19") (pinfunction "VSSA_19") (pintype "power_in"))
      (node (ref "U2") (pin "20") (pinfunction "VREF-_20") (pintype "power_in"))
      (node (ref "U2") (pin "27") (pinfunction "VSS_27") (pintype "power_in"))
      (node (ref "U2") (pin "41") (pinfunction "VSS_41") (pintype "power_in"))
      (node (ref "U2") (pin "47") (pinfunction "VSS_47") (pintype "power_in"))
      (node (ref "U2") (pin "99") (pinfunction "VSS_99") (pintype "power_in"))
      (node (ref "U3") (pin "2") (pinfunction "GND_2") (pintype "power_in"))
      (node (ref "U4") (pin "2") (pinfunction "GND_2") (pintype "power_in"))
      (node (ref "U5") (pin "1") (pinfunction "GND_1") (pintype "power_in"))
      (node (ref "U6") (pin "1") (pinfunction "GND_1") (pintype "power_in"))
    )
    (net (code "107") (name "Net-(C26-Pad2)") (class "Default")
      (node (ref "C26") (pin "2") (pinfunction "2_2") (pintype "passive"))
      (node (ref "P10") (pin "5") (pintype "passive"))
    )
    (net (code "108") (name "Net-(C27-Pad2)") (class "Default")
      (node (ref "C27") (pin "2") (pinfunction "2_2") (pintype "passive"))
      (node (ref "P10") (pin "4") (pintype "passive"))
    )
    (net (code "109") (name "Net-(D1-A)") (class "Default")
      (node (ref "D1") (pin "1") (pinfunction "A_1") (pintype "passive"))
      (node (ref "R1") (pin "2") (pintype "passive"))
    )
    (net (code "110") (name "Net-(D2-A)") (class "Default")
      (node (ref "D2") (pin "1") (pinfunction "A_1") (pintype "passive"))
      (node (ref "R4") (pin "2") (pintype "passive"))
    )
    (net (code "111") (name "Net-(D3-K)") (class "Default")
      (node (ref "D3") (pin "2") (pinfunction "K_2") (pintype "passive"))
      (node (ref "R9") (pin "1") (pintype "passive"))
    )
    (net (code "112") (name "Net-(P10-Pad9)") (class "Default")
      (node (ref "P10") (pin "9") (pintype "passive"))
      (node (ref "R21") (pin "2") (pintype "passive"))
    )
    (net (code "113") (name "Net-(P10-Pad12)") (class "Default")
      (node (ref "P10") (pin "12") (pintype "passive"))
      (node (ref "R22") (pin "2") (pintype "passive"))
    )
    (net (code "114") (name "Net-(R7-Pad2)") (class "Default")
      (node (ref "R7") (pin "2") (pintype "passive"))
      (node (ref "S2") (pin "2") (pinfunction "2_2") (pintype "passive"))
    )
    (net (code "115") (name "Net-(S1-COMMON)") (class "Default")
      (node (ref "F1") (pin "2") (pinfunction "2_2") (pintype "passive"))
      (node (ref "S1") (pin "1") (pinfunction "COMMON_1") (pintype "passive"))
    )
    (net (code "116") (name "Net-(U1-SW)") (class "Default")
      (node (ref "L1") (pin "1") (pinfunction "1_1") (pintype "passive"))
      (node (ref "U1") (pin "3") (pinfunction "SW_3") (pintype "output"))
    )
    (net (code "117") (name "Net-(U3-ISET)") (class "Default")
      (node (ref "R37") (pin "1") (pinfunction "1_1") (pintype "passive"))
      (node (ref "U3") (pin "5") (pinfunction "ISET_5") (pintype "bidirectional"))
    )
    (net (code "118") (name "Net-(U4-ISET)") (class "Default")
      (node (ref "R36") (pin "1") (pinfunction "1_1") (pintype "passive"))
      (node (ref "U4") (pin "5") (pinfunction "ISET_5") (pintype "bidirectional"))
    )
    (net (code "119") (name "VBUS") (class "Default")
      (node (ref "C34") (pin "1") (pinfunction "1_1") (pintype "passive"))
      (node (ref "C35") (pin "1") (pinfunction "1_1") (pintype "passive"))
      (node (ref "F1") (pin "1") (pinfunction "1_1") (pintype "passive"))
      (node (ref "P13") (pin "9") (pinfunction "9_9") (pintype "passive"))
      (node (ref "P8") (pin "5") (pinfunction "5_5") (pintype "passive"))
      (node (ref "P8") (pin "6") (pinfunction "6_6") (pintype "passive"))
      (node (ref "P8") (pin "7") (pinfunction "7_7") (pintype "passive"))
      (node (ref "P8") (pin "8") (pinfunction "8_8") (pintype "passive"))
      (node (ref "U3") (pin "6") (pinfunction "VIN_6") (pintype "power_in"))
      (node (ref "U4") (pin "6") (pinfunction "VIN_6") (pintype "power_in"))
      (node (ref "U5") (pin "2") (pinfunction "VO-_2") (pintype "power_in"))
      (node (ref "U6") (pin "2") (pinfunction "VO-_2") (pintype "power_in"))
    )
    (net (code "120") (name "VBUS_P1") (class "Default")
      (node (ref "C18") (pin "1") (pinfunction "1_1") (pintype "passive"))
      (node (ref "P4") (pin "1") (pinfunction "+5V_1") (pintype "power_in"))
      (node (ref "U4") (pin "1") (pinfunction "VOUT_1") (pintype "power_in"))
      (node (ref "U5") (pin "3") (pinfunction "VI+_3") (pintype "power_in"))
    )
    (net (code "121") (name "VBUS_P2") (class "Default")
      (node (ref "C11") (pin "1") (pinfunction "1_1") (pintype "passive"))
      (node (ref "P2") (pin "1") (pinfunction "+5V_1") (pintype "power_in"))
      (node (ref "U3") (pin "1") (pinfunction "VOUT_1") (pintype "power_in"))
      (node (ref "U6") (pin "3") (pinfunction "VI+_3") (pintype "power_in"))
    )
    (net (code "122") (name "VDD") (class "Default")
      (node (ref "C13") (pin "1") (pinfunction "1_1") (pintype "passive"))
      (node (ref "C19") (pin "2") (pinfunction "2_2") (pintype "passive"))
      (node (ref "C22") (pin "2") (pinfunction "2_2") (pintype "passive"))
      (node (ref "C23") (pin "2") (pinfunction "2_2") (pintype "passive"))
      (node (ref "C6") (pin "2") (pinfunction "2_2") (pintype "passive"))
      (node (ref "C8") (pin "1") (pinfunction "1_1") (pintype "passive"))
      (node (ref "D4") (pin "2") (pinfunction "K_2") (pintype "passive"))
      (node (ref "P13") (pin "7") (pinfunction "7_7") (pintype "passive"))
      (node (ref "P13") (pin "8") (pinfunction "8_8") (pintype "passive"))
      (node (ref "R1") (pin "1") (pintype "passive"))
      (node (ref "R2") (pin "1") (pintype "passive"))
      (node (ref "R23") (pin "1") (pintype "passive"))
      (node (ref "R4") (pin "1") (pintype "passive"))
      (node (ref "R6") (pin "2") (pinfunction "2_2") (pintype "passive"))
      (node (ref "U2") (pin "100") (pinfunction "VDD_100") (pintype "power_in"))
      (node (ref "U2") (pin "11") (pinfunction "VDD_11") (pintype "power_in"))
      (node (ref "U2") (pin "28") (pinfunction "VDD_28") (pintype "power_in"))
      (node (ref "U2") (pin "46") (pinfunction "VDD_46") (pintype "power_in"))
      (node (ref "U2") (pin "75") (pinfunction "VDD_75") (pintype "power_in"))
    )
    (net (code "123") (name "unconnected-(C24-Pad1)") (class "Default")
      (node (ref "C24") (pin "1") (pinfunction "1_1") (pintype "passive"))
    )
    (net (code "124") (name "unconnected-(D4-A-Pad1)") (class "Default")
      (node (ref "D4") (pin "1") (pinfunction "A_1") (pintype "passive"))
    )
    (net (code "125") (name "unconnected-(P10-Pad7)") (class "Default")
      (node (ref "P10") (pin "7") (pintype "passive"))
    )
    (net (code "126") (name "unconnected-(S1-NO-Pad3)") (class "Default")
      (node (ref "S1") (pin "3") (pinfunction "NO_3") (pintype "passive"))
    )
    (net (code "127") (name "unconnected-(U1-NC.-Pad1)") (class "Default")
      (node (ref "U1") (pin "1") (pinfunction "NC._1") (pintype "passive"))
    )
    (net (code "128") (name "unconnected-(U3-FLAG#-Pad3)") (class "Default")
      (node (ref "U3") (pin "3") (pinfunction "FLAG#_3") (pintype "open_collector+no_connect"))
    )
    (net (code "129") (name "unconnected-(U4-FLAG#-Pad3)") (class "Default")
      (node (ref "U4") (pin "3") (pinfunction "FLAG#_3") (pintype "open_collector+no_connect"))
    )
  )
)
